# ICSP_Pogo_Connector.net
KiCad netlist of a schematic drawn in EAGLE
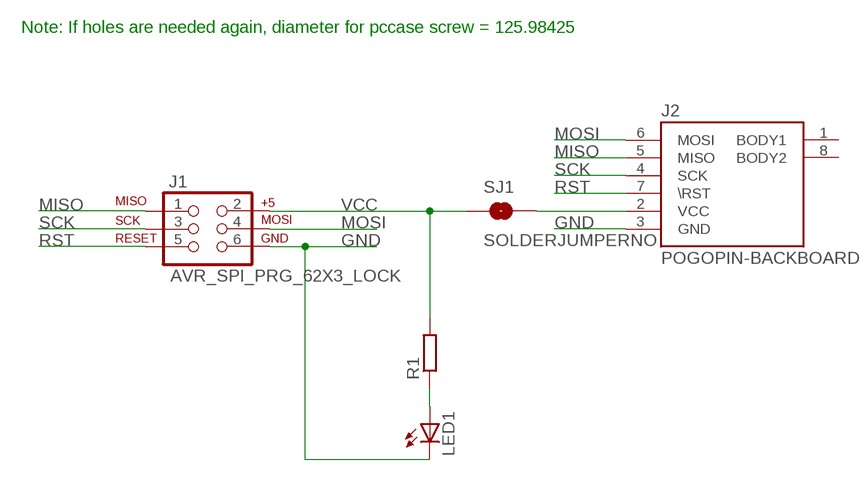
[diagram p0: schematic, sheet 1]

(export (version "E")
  (design (tool "Eeschema 10.0.6"))
  (components
    (comp (ref "J1")
      (value "AVR_SPI_PRG_62X3_LOCK")
      (footprint "eagle-import:2X3_LOCK")
      (libsource (lib "eagle-import") (part "AVR_SPI_PRG_62X3_LOCK"))
    )
    (comp (ref "J2")
      (value "POGOPIN-BACKBOARD")
      (footprint "eagle-import:POGOPROG-BACKMOUNT")
      (libsource (lib "eagle-import") (part "POGOPIN-BACKBOARD"))
    )
    (comp (ref "LED1")
      (value "LEDCHIP-LED0805")
      (footprint "eagle-import:CHIP-LED0805")
      (libsource (lib "eagle-import") (part "LEDCHIP-LED0805"))
    )
    (comp (ref "R1")
      (value "R-EU_M0805")
      (footprint "eagle-import:M0805")
      (libsource (lib "eagle-import") (part "R-EU_M0805"))
    )
    (comp (ref "SJ1")
      (value "SOLDERJUMPERNO")
      (footprint "eagle-import:SJ_2S-NO")
      (libsource (lib "eagle-import") (part "SOLDERJUMPERNO"))
    )
  )
  (nets
    (net (code "1") (name "/GND") (class "Default")
      (node (ref "J1") (pin "6") (pinfunction "6_6") (pintype "passive"))
      (node (ref "J2") (pin "3") (pinfunction "GND_3") (pintype "bidirectional"))
      (node (ref "LED1") (pin "C") (pinfunction "C_C") (pintype "passive"))
    )
    (net (code "2") (name "/MISO") (class "Default")
      (node (ref "J1") (pin "1") (pinfunction "1_1") (pintype "passive"))
      (node (ref "J2") (pin "5") (pinfunction "MISO_5") (pintype "bidirectional"))
    )
    (net (code "3") (name "/MOSI") (class "Default")
      (node (ref "J1") (pin "4") (pinfunction "4_4") (pintype "passive"))
      (node (ref "J2") (pin "6") (pinfunction "MOSI_6") (pintype "bidirectional"))
    )
    (net (code "4") (name "/RST") (class "Default")
      (node (ref "J1") (pin "5") (pinfunction "5_5") (pintype "passive"))
      (node (ref "J2") (pin "7") (pinfunction "\\RST_7") (pintype "bidirectional"))
    )
    (net (code "5") (name "/SCK") (class "Default")
      (node (ref "J1") (pin "3") (pinfunction "3_3") (pintype "passive"))
      (node (ref "J2") (pin "4") (pinfunction "SCK_4") (pintype "bidirectional"))
    )
    (net (code "6") (name "/VCC") (class "Default")
      (node (ref "J1") (pin "2") (pinfunction "2_2") (pintype "passive"))
      (node (ref "R1") (pin "2") (pinfunction "2_2") (pintype "passive"))
      (node (ref "SJ1") (pin "1") (pinfunction "1_1") (pintype "passive"))
    )
    (net (code "7") (name "Net-(J2-VCC)") (class "Default")
      (node (ref "J2") (pin "2") (pinfunction "VCC_2") (pintype "bidirectional"))
      (node (ref "SJ1") (pin "2") (pinfunction "2_2") (pintype "passive"))
    )
    (net (code "8") (name "Net-(LED1-PadA)") (class "Default")
      (node (ref "LED1") (pin "A") (pinfunction "A_A") (pintype "passive"))
      (node (ref "R1") (pin "1") (pinfunction "1_1") (pintype "passive"))
    )
    (net (code "9") (name "unconnected-(J2-BODY1-Pad1)") (class "Default")
      (node (ref "J2") (pin "1") (pinfunction "BODY1_1") (pintype "bidirectional"))
    )
    (net (code "10") (name "unconnected-(J2-BODY2-Pad8)") (class "Default")
      (node (ref "J2") (pin "8") (pinfunction "BODY2_8") (pintype "bidirectional"))
    )
  )
)
